# Pinguino-Schematics.net
KiCad netlist of a schematic drawn in Altium Designer
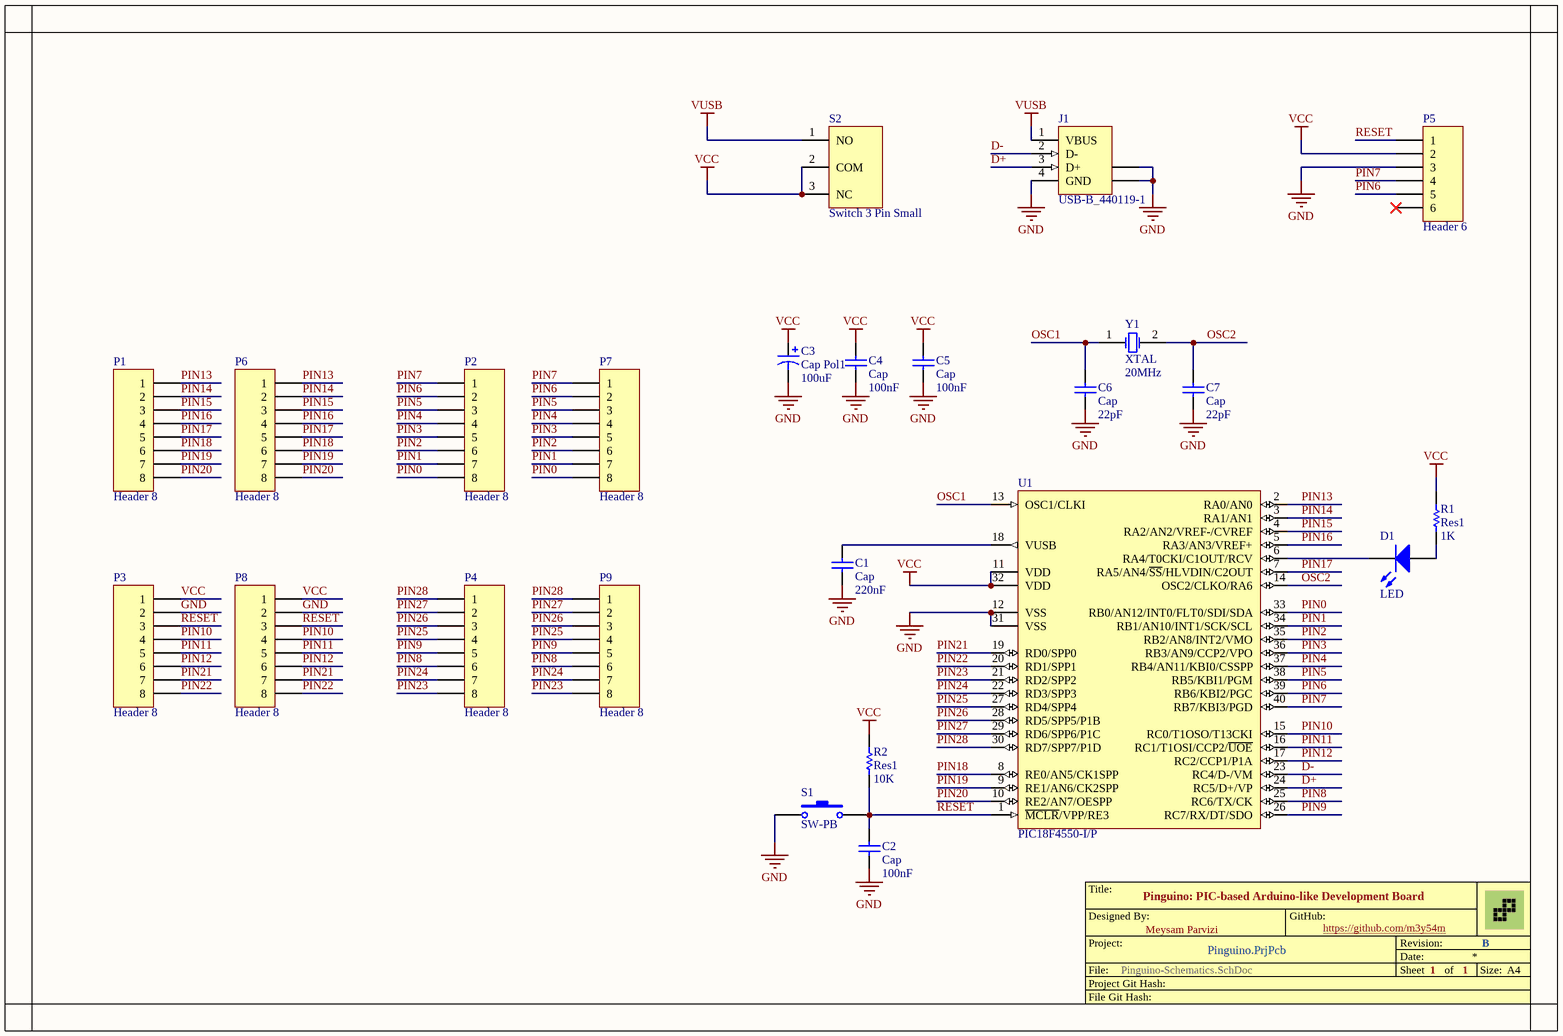
[diagram p0: Pinguino-Schematics.SchDoc]

(export (version "E")
  (design (tool "Eeschema 10.0.6"))
  (components
    (comp (ref "C1")
      (value "Cap")
      (footprint "C1206")
      (description "Capacitor")
      (fields (field (name "ALTIUM_VALUE") "220nF") (field (name "PUBLISHER") "Altium Limited"))
      (libsource (lib "Miscellaneous Devices") (part "Cap"))
    )
    (comp (ref "C2")
      (value "Cap")
      (footprint "C1206")
      (description "Capacitor")
      (fields (field (name "ALTIUM_VALUE") "100nF") (field (name "PUBLISHER") "Altium Limited"))
      (libsource (lib "Miscellaneous Devices") (part "Cap"))
    )
    (comp (ref "C3")
      (value "Cap Pol1")
      (footprint "CAP1")
      (description "Polarized Capacitor (Radial)")
      (fields (field (name "ALTIUM_VALUE") "100uF") (field (name "PUBLISHER") "Altium Limited"))
      (libsource (lib "Miscellaneous Devices") (part "Cap Pol1"))
    )
    (comp (ref "C4")
      (value "Cap")
      (footprint "C1206")
      (description "Capacitor")
      (fields (field (name "ALTIUM_VALUE") "100nF") (field (name "PUBLISHER") "Altium Limited"))
      (libsource (lib "Miscellaneous Devices") (part "Cap"))
    )
    (comp (ref "C5")
      (value "Cap")
      (footprint "C1206")
      (description "Capacitor")
      (fields (field (name "ALTIUM_VALUE") "100nF") (field (name "PUBLISHER") "Altium Limited"))
      (libsource (lib "Miscellaneous Devices") (part "Cap"))
    )
    (comp (ref "C6")
      (value "Cap")
      (footprint "C1206")
      (description "Capacitor")
      (fields (field (name "ALTIUM_VALUE") "22pF") (field (name "PUBLISHER") "Altium Limited"))
      (libsource (lib "Miscellaneous Devices") (part "Cap"))
    )
    (comp (ref "C7")
      (value "Cap")
      (footprint "C1206")
      (description "Capacitor")
      (fields (field (name "ALTIUM_VALUE") "22pF") (field (name "PUBLISHER") "Altium Limited"))
      (libsource (lib "Miscellaneous Devices") (part "Cap"))
    )
    (comp (ref "D1")
      (value "LED")
      (footprint "LED0")
      (description "Typical RED GaAs LED")
      (fields (field (name "DESIGNER") "Meysam Parvizi") (field (name "EMAIL") "meysam.parvizi.ir@gmail.com"))
      (libsource (lib "mp") (part "LED"))
    )
    (comp (ref "J1")
      (value "USB-B_440119-1")
      (footprint "USB-B")
      (description "USB 1.1, Right Angle, Thru-Hole, B Type, Receptacle, 4 Position, Beige")
      (fields (field (name "PUBLISHER") "Altium Limited"))
      (libsource (lib "mp") (part "USB-B_440119-1"))
    )
    (comp (ref "P1")
      (value "Header 8")
      (footprint "HDR1X8")
      (description "Header, 8-Pin")
      (fields (field (name "PUBLISHER") "Altium Limited"))
      (libsource (lib "") (part "Header 8_1"))
    )
    (comp (ref "P2")
      (value "Header 8")
      (footprint "HDR1X8")
      (description "Header, 8-Pin")
      (fields (field (name "PUBLISHER") "Altium Limited"))
      (libsource (lib "Miscellaneous Connectors") (part "Header 8"))
    )
    (comp (ref "P3")
      (value "Header 8")
      (footprint "HDR1X8")
      (description "Header, 8-Pin")
      (fields (field (name "PUBLISHER") "Altium Limited"))
      (libsource (lib "") (part "Header 8_1"))
    )
    (comp (ref "P4")
      (value "Header 8")
      (footprint "HDR1X8")
      (description "Header, 8-Pin")
      (fields (field (name "PUBLISHER") "Altium Limited"))
      (libsource (lib "Miscellaneous Connectors") (part "Header 8"))
    )
    (comp (ref "P5")
      (value "Header 6")
      (footprint "HDR1X6")
      (description "Header, 6-Pin")
      (fields (field (name "PUBLISHER") "Altium Limited"))
      (libsource (lib "Miscellaneous Connectors") (part "Header 6"))
    )
    (comp (ref "P6")
      (value "Header 8")
      (footprint "HDR1X8")
      (description "Header, 8-Pin")
      (fields (field (name "PUBLISHER") "Altium Limited"))
      (libsource (lib "") (part "Header 8_1"))
    )
    (comp (ref "P7")
      (value "Header 8")
      (footprint "HDR1X8")
      (description "Header, 8-Pin")
      (fields (field (name "PUBLISHER") "Altium Limited"))
      (libsource (lib "Miscellaneous Connectors") (part "Header 8"))
    )
    (comp (ref "P8")
      (value "Header 8")
      (footprint "HDR1X8")
      (description "Header, 8-Pin")
      (fields (field (name "PUBLISHER") "Altium Limited"))
      (libsource (lib "") (part "Header 8_1"))
    )
    (comp (ref "P9")
      (value "Header 8")
      (footprint "HDR1X8")
      (description "Header, 8-Pin")
      (fields (field (name "PUBLISHER") "Altium Limited"))
      (libsource (lib "Miscellaneous Connectors") (part "Header 8"))
    )
    (comp (ref "R1")
      (value "Res1")
      (footprint "C1206")
      (description "Resistor")
      (fields (field (name "ALTIUM_VALUE") "1K") (field (name "PUBLISHER") "Altium Limited"))
      (libsource (lib "Miscellaneous Devices") (part "Res1"))
    )
    (comp (ref "R2")
      (value "Res1")
      (footprint "C1206")
      (description "Resistor")
      (fields (field (name "ALTIUM_VALUE") "10K") (field (name "PUBLISHER") "Altium Limited"))
      (libsource (lib "Miscellaneous Devices") (part "Res1"))
    )
    (comp (ref "S1")
      (value "SW-PB")
      (footprint "PUSH0")
      (description "Switch")
      (fields (field (name "PUBLISHER") "Altium Limited"))
      (libsource (lib "mp") (part "SW-PB"))
    )
    (comp (ref "S2")
      (value "Switch 3 Pin Small")
      (footprint "SW_ON_OFF_SMALL")
      (description "Switch 3 Pin")
      (fields (field (name "DESIGNER") "Meysam Parvizi") (field (name "EMAIL") "meysam.parvizi.ir@gmail.com"))
      (libsource (lib "mp") (part "Switch 3 Pin Small"))
    )
    (comp (ref "U1")
      (value "PIC18F4550-I/P")
      (footprint "PDIP600-P40")
      (fields (field (name "PUBLISHER") "Altium Limited"))
      (libsource (lib "Microchip Microcontroller 8-Bit PIC18") (part "PIC18F4550-I/P"))
    )
    (comp (ref "Y1")
      (value "XTAL")
      (footprint "XTAL")
      (description "Crystal Oscillator")
      (fields
        (field (name "ALTIUM_VALUE") "20MHz")
        (field (name "DESIGNER") "Meysam Parvizi")
        (field (name "EMAIL") "meysam.parvizi.ir@gmail.com")
      )
      (libsource (lib "mp") (part "XTAL"))
    )
  )
  (nets
    (net (code "1") (name "/D+") (class "Default")
      (node (ref "J1") (pin "3") (pinfunction "D+_3") (pintype "input"))
      (node (ref "U1") (pin "24") (pinfunction "RC5/D+/VP_24") (pintype "bidirectional"))
    )
    (net (code "2") (name "/D-") (class "Default")
      (node (ref "J1") (pin "2") (pinfunction "D-_2") (pintype "input"))
      (node (ref "U1") (pin "23") (pinfunction "RC4/D-/VM_23") (pintype "bidirectional"))
    )
    (net (code "3") (name "/OSC1") (class "Default")
      (node (ref "C6") (pin "2") (pinfunction "2_2") (pintype "passive"))
      (node (ref "U1") (pin "13") (pinfunction "OSC1/CLKI_13") (pintype "input"))
      (node (ref "Y1") (pin "1") (pinfunction "OSC1_1") (pintype "passive"))
    )
    (net (code "4") (name "/OSC2") (class "Default")
      (node (ref "C7") (pin "2") (pinfunction "2_2") (pintype "passive"))
      (node (ref "U1") (pin "14") (pinfunction "OSC2/CLKO/RA6_14") (pintype "bidirectional"))
      (node (ref "Y1") (pin "2") (pinfunction "OSC2_2") (pintype "passive"))
    )
    (net (code "5") (name "/PIN0") (class "Default")
      (node (ref "P2") (pin "8") (pinfunction "8_8") (pintype "passive"))
      (node (ref "P7") (pin "8") (pinfunction "8_8") (pintype "passive"))
      (node (ref "U1") (pin "33") (pinfunction "RB0/AN12/INT0/FLT0/SDI/SDA_33") (pintype "bidirectional"))
    )
    (net (code "6") (name "/PIN1") (class "Default")
      (node (ref "P2") (pin "7") (pinfunction "7_7") (pintype "passive"))
      (node (ref "P7") (pin "7") (pinfunction "7_7") (pintype "passive"))
      (node (ref "U1") (pin "34") (pinfunction "RB1/AN10/INT1/SCK/SCL_34") (pintype "bidirectional"))
    )
    (net (code "7") (name "/PIN2") (class "Default")
      (node (ref "P2") (pin "6") (pinfunction "6_6") (pintype "passive"))
      (node (ref "P7") (pin "6") (pinfunction "6_6") (pintype "passive"))
      (node (ref "U1") (pin "35") (pinfunction "RB2/AN8/INT2/VMO_35") (pintype "bidirectional"))
    )
    (net (code "8") (name "/PIN3") (class "Default")
      (node (ref "P2") (pin "5") (pinfunction "5_5") (pintype "passive"))
      (node (ref "P7") (pin "5") (pinfunction "5_5") (pintype "passive"))
      (node (ref "U1") (pin "36") (pinfunction "RB3/AN9/CCP2/VPO_36") (pintype "bidirectional"))
    )
    (net (code "9") (name "/PIN4") (class "Default")
      (node (ref "P2") (pin "4") (pinfunction "4_4") (pintype "passive"))
      (node (ref "P7") (pin "4") (pinfunction "4_4") (pintype "passive"))
      (node (ref "U1") (pin "37") (pinfunction "RB4/AN11/KBI0/CSSPP_37") (pintype "bidirectional"))
    )
    (net (code "10") (name "/PIN5") (class "Default")
      (node (ref "P2") (pin "3") (pinfunction "3_3") (pintype "passive"))
      (node (ref "P7") (pin "3") (pinfunction "3_3") (pintype "passive"))
      (node (ref "U1") (pin "38") (pinfunction "RB5/KBI1/PGM_38") (pintype "bidirectional"))
    )
    (net (code "11") (name "/PIN6") (class "Default")
      (node (ref "P2") (pin "2") (pinfunction "2_2") (pintype "passive"))
      (node (ref "P5") (pin "5") (pinfunction "5_5") (pintype "passive"))
      (node (ref "P7") (pin "2") (pinfunction "2_2") (pintype "passive"))
      (node (ref "U1") (pin "39") (pinfunction "RB6/KBI2/PGC_39") (pintype "bidirectional"))
    )
    (net (code "12") (name "/PIN7") (class "Default")
      (node (ref "P2") (pin "1") (pinfunction "1_1") (pintype "passive"))
      (node (ref "P5") (pin "4") (pinfunction "4_4") (pintype "passive"))
      (node (ref "P7") (pin "1") (pinfunction "1_1") (pintype "passive"))
      (node (ref "U1") (pin "40") (pinfunction "RB7/KBI3/PGD_40") (pintype "bidirectional"))
    )
    (net (code "13") (name "/PIN8") (class "Default")
      (node (ref "P4") (pin "6") (pinfunction "6_6") (pintype "passive"))
      (node (ref "P9") (pin "6") (pinfunction "6_6") (pintype "passive"))
      (node (ref "U1") (pin "25") (pinfunction "RC6/TX/CK_25") (pintype "bidirectional"))
    )
    (net (code "14") (name "/PIN9") (class "Default")
      (node (ref "P4") (pin "5") (pinfunction "5_5") (pintype "passive"))
      (node (ref "P9") (pin "5") (pinfunction "5_5") (pintype "passive"))
      (node (ref "U1") (pin "26") (pinfunction "RC7/RX/DT/SDO_26") (pintype "bidirectional"))
    )
    (net (code "15") (name "/PIN10") (class "Default")
      (node (ref "P3") (pin "4") (pinfunction "4_4") (pintype "passive"))
      (node (ref "P8") (pin "4") (pinfunction "4_4") (pintype "passive"))
      (node (ref "U1") (pin "15") (pinfunction "RC0/T1OSO/T13CKI_15") (pintype "bidirectional"))
    )
    (net (code "16") (name "/PIN11") (class "Default")
      (node (ref "P3") (pin "5") (pinfunction "5_5") (pintype "passive"))
      (node (ref "P8") (pin "5") (pinfunction "5_5") (pintype "passive"))
      (node (ref "U1") (pin "16") (pinfunction "RC1/T1OSI/CCP2/~{UOE}_16") (pintype "bidirectional"))
    )
    (net (code "17") (name "/PIN12") (class "Default")
      (node (ref "P3") (pin "6") (pinfunction "6_6") (pintype "passive"))
      (node (ref "P8") (pin "6") (pinfunction "6_6") (pintype "passive"))
      (node (ref "U1") (pin "17") (pinfunction "RC2/CCP1/P1A_17") (pintype "bidirectional"))
    )
    (net (code "18") (name "/PIN13") (class "Default")
      (node (ref "P1") (pin "1") (pinfunction "1_1") (pintype "passive"))
      (node (ref "P6") (pin "1") (pinfunction "1_1") (pintype "passive"))
      (node (ref "U1") (pin "2") (pinfunction "RA0/AN0_2") (pintype "bidirectional"))
    )
    (net (code "19") (name "/PIN14") (class "Default")
      (node (ref "P1") (pin "2") (pinfunction "2_2") (pintype "passive"))
      (node (ref "P6") (pin "2") (pinfunction "2_2") (pintype "passive"))
      (node (ref "U1") (pin "3") (pinfunction "RA1/AN1_3") (pintype "bidirectional"))
    )
    (net (code "20") (name "/PIN15") (class "Default")
      (node (ref "P1") (pin "3") (pinfunction "3_3") (pintype "passive"))
      (node (ref "P6") (pin "3") (pinfunction "3_3") (pintype "passive"))
      (node (ref "U1") (pin "4") (pinfunction "RA2/AN2/VREF-/CVREF_4") (pintype "bidirectional"))
    )
    (net (code "21") (name "/PIN16") (class "Default")
      (node (ref "P1") (pin "4") (pinfunction "4_4") (pintype "passive"))
      (node (ref "P6") (pin "4") (pinfunction "4_4") (pintype "passive"))
      (node (ref "U1") (pin "5") (pinfunction "RA3/AN3/VREF+_5") (pintype "bidirectional"))
    )
    (net (code "22") (name "/PIN17") (class "Default")
      (node (ref "P1") (pin "5") (pinfunction "5_5") (pintype "passive"))
      (node (ref "P6") (pin "5") (pinfunction "5_5") (pintype "passive"))
      (node (ref "U1") (pin "7") (pinfunction "RA5/AN4/~{SS}/HLVDIN/C2OUT_7") (pintype "bidirectional"))
    )
    (net (code "23") (name "/PIN18") (class "Default")
      (node (ref "P1") (pin "6") (pinfunction "6_6") (pintype "passive"))
      (node (ref "P6") (pin "6") (pinfunction "6_6") (pintype "passive"))
      (node (ref "U1") (pin "8") (pinfunction "RE0/AN5/CK1SPP_8") (pintype "bidirectional"))
    )
    (net (code "24") (name "/PIN19") (class "Default")
      (node (ref "P1") (pin "7") (pinfunction "7_7") (pintype "passive"))
      (node (ref "P6") (pin "7") (pinfunction "7_7") (pintype "passive"))
      (node (ref "U1") (pin "9") (pinfunction "RE1/AN6/CK2SPP_9") (pintype "bidirectional"))
    )
    (net (code "25") (name "/PIN20") (class "Default")
      (node (ref "P1") (pin "8") (pinfunction "8_8") (pintype "passive"))
      (node (ref "P6") (pin "8") (pinfunction "8_8") (pintype "passive"))
      (node (ref "U1") (pin "10") (pinfunction "RE2/AN7/OESPP_10") (pintype "bidirectional"))
    )
    (net (code "26") (name "/PIN21") (class "Default")
      (node (ref "P3") (pin "7") (pinfunction "7_7") (pintype "passive"))
      (node (ref "P8") (pin "7") (pinfunction "7_7") (pintype "passive"))
      (node (ref "U1") (pin "19") (pinfunction "RD0/SPP0_19") (pintype "bidirectional"))
    )
    (net (code "27") (name "/PIN22") (class "Default")
      (node (ref "P3") (pin "8") (pinfunction "8_8") (pintype "passive"))
      (node (ref "P8") (pin "8") (pinfunction "8_8") (pintype "passive"))
      (node (ref "U1") (pin "20") (pinfunction "RD1/SPP1_20") (pintype "bidirectional"))
    )
    (net (code "28") (name "/PIN23") (class "Default")
      (node (ref "P4") (pin "8") (pinfunction "8_8") (pintype "passive"))
      (node (ref "P9") (pin "8") (pinfunction "8_8") (pintype "passive"))
      (node (ref "U1") (pin "21") (pinfunction "RD2/SPP2_21") (pintype "bidirectional"))
    )
    (net (code "29") (name "/PIN24") (class "Default")
      (node (ref "P4") (pin "7") (pinfunction "7_7") (pintype "passive"))
      (node (ref "P9") (pin "7") (pinfunction "7_7") (pintype "passive"))
      (node (ref "U1") (pin "22") (pinfunction "RD3/SPP3_22") (pintype "bidirectional"))
    )
    (net (code "30") (name "/PIN25") (class "Default")
      (node (ref "P4") (pin "4") (pinfunction "4_4") (pintype "passive"))
      (node (ref "P9") (pin "4") (pinfunction "4_4") (pintype "passive"))
      (node (ref "U1") (pin "27") (pinfunction "RD4/SPP4_27") (pintype "bidirectional"))
    )
    (net (code "31") (name "/PIN26") (class "Default")
      (node (ref "P4") (pin "3") (pinfunction "3_3") (pintype "passive"))
      (node (ref "P9") (pin "3") (pinfunction "3_3") (pintype "passive"))
      (node (ref "U1") (pin "28") (pinfunction "RD5/SPP5/P1B_28") (pintype "bidirectional"))
    )
    (net (code "32") (name "/PIN27") (class "Default")
      (node (ref "P4") (pin "2") (pinfunction "2_2") (pintype "passive"))
      (node (ref "P9") (pin "2") (pinfunction "2_2") (pintype "passive"))
      (node (ref "U1") (pin "29") (pinfunction "RD6/SPP6/P1C_29") (pintype "bidirectional"))
    )
    (net (code "33") (name "/PIN28") (class "Default")
      (node (ref "P4") (pin "1") (pinfunction "1_1") (pintype "passive"))
      (node (ref "P9") (pin "1") (pinfunction "1_1") (pintype "passive"))
      (node (ref "U1") (pin "30") (pinfunction "RD7/SPP7/P1D_30") (pintype "bidirectional"))
    )
    (net (code "34") (name "/RESET") (class "Default")
      (node (ref "C2") (pin "2") (pinfunction "2_2") (pintype "passive"))
      (node (ref "P3") (pin "3") (pinfunction "3_3") (pintype "passive"))
      (node (ref "P5") (pin "1") (pinfunction "1_1") (pintype "passive"))
      (node (ref "P8") (pin "3") (pinfunction "3_3") (pintype "passive"))
      (node (ref "R2") (pin "1") (pinfunction "1_1") (pintype "passive"))
      (node (ref "S1") (pin "2") (pinfunction "2_2") (pintype "passive"))
      (node (ref "U1") (pin "1") (pinfunction "~{MCLR}/VPP/RE3_1") (pintype "input"))
    )
    (net (code "35") (name "GND") (class "Default")
      (node (ref "C1") (pin "1") (pinfunction "1_1") (pintype "passive"))
      (node (ref "C2") (pin "1") (pinfunction "1_1") (pintype "passive"))
      (node (ref "C3") (pin "2") (pinfunction "2_2") (pintype "passive"))
      (node (ref "C4") (pin "1") (pinfunction "1_1") (pintype "passive"))
      (node (ref "C5") (pin "1") (pinfunction "1_1") (pintype "passive"))
      (node (ref "C6") (pin "1") (pinfunction "1_1") (pintype "passive"))
      (node (ref "C7") (pin "1") (pinfunction "1_1") (pintype "passive"))
      (node (ref "J1") (pin "4") (pinfunction "GND_4") (pintype "power_in"))
      (node (ref "J1") (pin "5") (pinfunction "SHLD_5") (pintype "passive"))
      (node (ref "J1") (pin "6") (pinfunction "SHLD_6") (pintype "passive"))
      (node (ref "P3") (pin "2") (pinfunction "2_2") (pintype "passive"))
      (node (ref "P5") (pin "3") (pinfunction "3_3") (pintype "passive"))
      (node (ref "P8") (pin "2") (pinfunction "2_2") (pintype "passive"))
      (node (ref "S1") (pin "1") (pinfunction "1_1") (pintype "passive"))
      (node (ref "U1") (pin "12") (pinfunction "VSS_12") (pintype "power_in"))
      (node (ref "U1") (pin "31") (pinfunction "VSS_31") (pintype "power_in"))
    )
    (net (code "36") (name "Net-(D1-A)") (class "Default")
      (node (ref "D1") (pin "1") (pinfunction "A_1") (pintype "passive"))
      (node (ref "R1") (pin "1") (pinfunction "1_1") (pintype "passive"))
    )
    (net (code "37") (name "Net-(D1-K)") (class "Default")
      (node (ref "D1") (pin "2") (pinfunction "K_2") (pintype "passive"))
      (node (ref "U1") (pin "6") (pinfunction "RA4/T0CKI/C1OUT/RCV_6") (pintype "bidirectional"))
    )
    (net (code "38") (name "Net-(U1-VUSB)") (class "Default")
      (node (ref "C1") (pin "2") (pinfunction "2_2") (pintype "passive"))
      (node (ref "U1") (pin "18") (pinfunction "VUSB_18") (pintype "output"))
    )
    (net (code "39") (name "VCC") (class "Default")
      (node (ref "C3") (pin "1") (pinfunction "1_1") (pintype "passive"))
      (node (ref "C4") (pin "2") (pinfunction "2_2") (pintype "passive"))
      (node (ref "C5") (pin "2") (pinfunction "2_2") (pintype "passive"))
      (node (ref "P3") (pin "1") (pinfunction "1_1") (pintype "passive"))
      (node (ref "P5") (pin "2") (pinfunction "2_2") (pintype "passive"))
      (node (ref "P8") (pin "1") (pinfunction "1_1") (pintype "passive"))
      (node (ref "R1") (pin "2") (pinfunction "2_2") (pintype "passive"))
      (node (ref "R2") (pin "2") (pinfunction "2_2") (pintype "passive"))
      (node (ref "S2") (pin "2") (pinfunction "COM_2") (pintype "power_in"))
      (node (ref "S2") (pin "3") (pinfunction "NC_3") (pintype "passive"))
      (node (ref "U1") (pin "11") (pinfunction "VDD_11") (pintype "power_in"))
      (node (ref "U1") (pin "32") (pinfunction "VDD_32") (pintype "power_in"))
    )
    (net (code "40") (name "VUSB") (class "Default")
      (node (ref "J1") (pin "1") (pinfunction "VBUS_1") (pintype "power_in"))
      (node (ref "S2") (pin "1") (pinfunction "NO_1") (pintype "passive"))
    )
    (net (code "41") (name "unconnected-(P5-Pad6)") (class "Default")
      (node (ref "P5") (pin "6") (pinfunction "6_6") (pintype "passive+no_connect"))
    )
  )
)
